# Half_Slave.net
KiCad netlist of a schematic drawn in Altium Designer
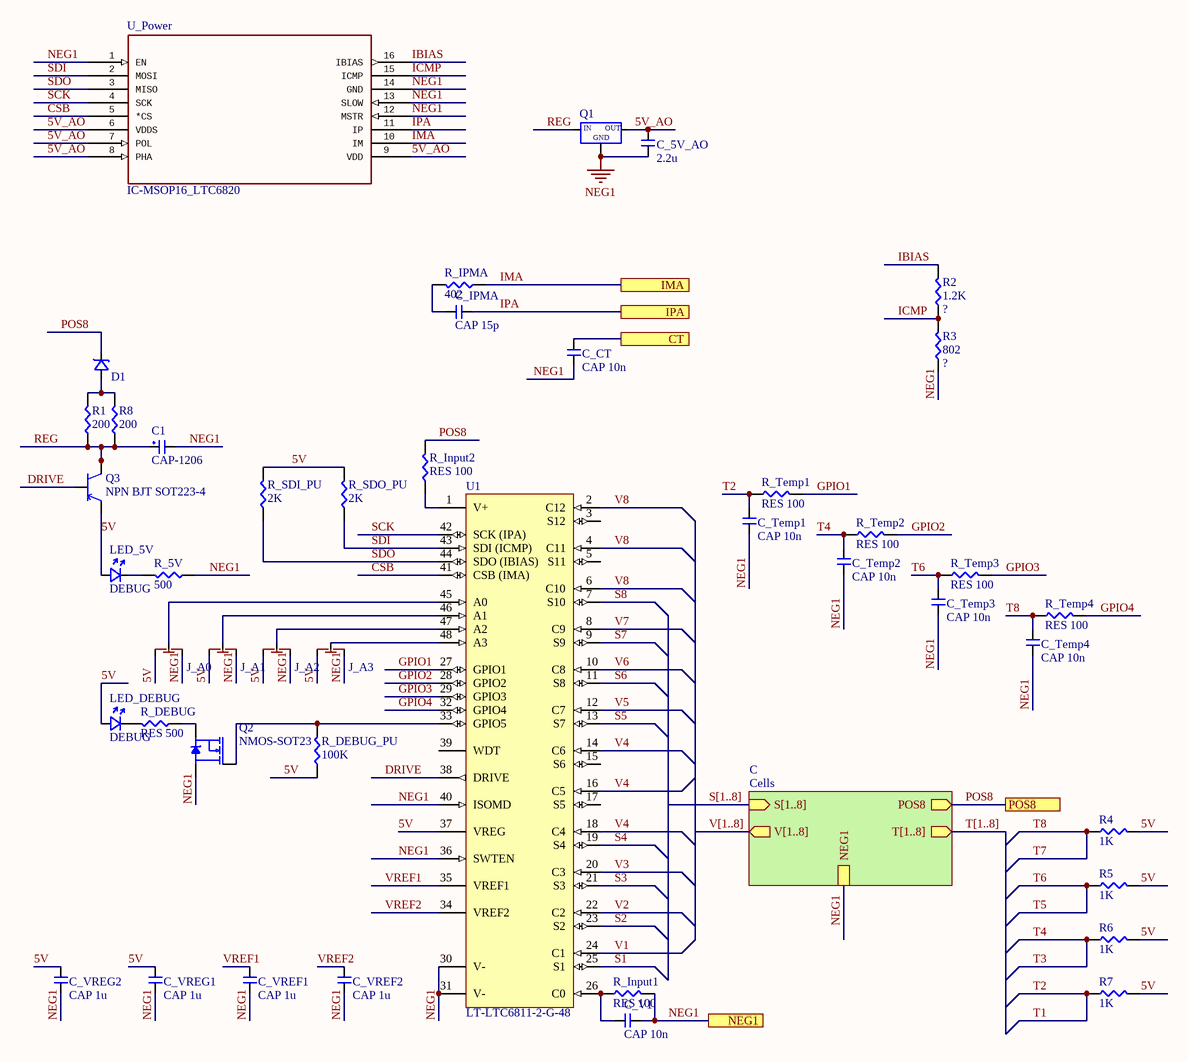
[diagram p0: Half_Slave.SchDoc]

(export (version "E")
  (design (tool "Eeschema 10.0.6"))
  (components
    (comp (ref "C1")
      (value "CAP-1206")
      (footprint "CAPCP3216X16N")
      (libsource (lib "LTC6811") (part "CAP-1206"))
    )
    (comp (ref "C_5V_AO")
      (value "2.2u")
      (footprint "CAP-0603")
      (description "CAP-0603")
      (libsource (lib "ife19_Elec_Library") (part "CAP-0603"))
    )
    (comp (ref "C_CT")
      (value "CAP 10n")
      (footprint "CAP-0603")
      (description "CAP-0603")
      (libsource (lib "ife18_TS_BMS_LTC6813_v2_Library") (part "CAP-0603"))
    )
    (comp (ref "C_IPMA")
      (value "CAP 15p")
      (footprint "CAP-0603")
      (description "CAP-0603")
      (libsource (lib "ife19_Elec_Library") (part "CAP-0603"))
    )
    (comp (ref "C_Temp1")
      (value "CAP 10n")
      (footprint "CAP-0603")
      (description "CAP-0603")
      (libsource (lib "altium-import") (part "root_1_CAP-0603_"))
    )
    (comp (ref "C_Temp2")
      (value "CAP 10n")
      (footprint "CAP-0603")
      (description "CAP-0603")
      (libsource (lib "altium-import") (part "root_1_CAP-0603_"))
    )
    (comp (ref "C_Temp3")
      (value "CAP 10n")
      (footprint "CAP-0603")
      (description "CAP-0603")
      (libsource (lib "altium-import") (part "root_1_CAP-0603_"))
    )
    (comp (ref "C_Temp4")
      (value "CAP 10n")
      (footprint "CAP-0603")
      (description "CAP-0603")
      (libsource (lib "altium-import") (part "root_1_CAP-0603_"))
    )
    (comp (ref "C_V1")
      (value "CAP 10n")
      (footprint "CAP-0603")
      (description "CAP-0603")
      (libsource (lib "altium-import") (part "root_2_CAP-0603_"))
    )
    (comp (ref "C_VREF1")
      (value "CAP 1u")
      (footprint "CAP-0603")
      (description "CAP-0603")
      (libsource (lib "altium-import") (part "root_1_CAP-0603_"))
    )
    (comp (ref "C_VREF2")
      (value "CAP 1u")
      (footprint "CAP-0603")
      (description "CAP-0603")
      (libsource (lib "altium-import") (part "root_1_CAP-0603_"))
    )
    (comp (ref "C_VREG1")
      (value "CAP 1u")
      (footprint "CAP-0603")
      (description "CAP-0603")
      (libsource (lib "altium-import") (part "root_1_CAP-0603_"))
    )
    (comp (ref "C_VREG2")
      (value "CAP 1u")
      (footprint "CAP-0603")
      (description "CAP-0603")
      (libsource (lib "altium-import") (part "root_1_CAP-0603_"))
    )
    (comp (ref "D1") (value "?") (footprint "SMB") (libsource (lib "ife19_Elec_Library") (part "DIODE-SMB")))
    (comp (ref "J_A0")
      (value "DPDT Solder Jumper")
      (footprint "DPDT Solder")
      (libsource (lib "LTC6811") (part "DPDT Solder"))
    )
    (comp (ref "J_A1")
      (value "DPDT Solder Jumper")
      (footprint "DPDT Solder")
      (libsource (lib "LTC6811") (part "DPDT Solder"))
    )
    (comp (ref "J_A2")
      (value "DPDT Solder Jumper")
      (footprint "DPDT Solder")
      (libsource (lib "LTC6811") (part "DPDT Solder"))
    )
    (comp (ref "J_A3")
      (value "DPDT Solder Jumper")
      (footprint "DPDT Solder")
      (libsource (lib "LTC6811") (part "DPDT Solder"))
    )
    (comp (ref "LED_5V")
      (value "DEBUG")
      (footprint "LED-0603")
      (description "LED-0603")
      (libsource (lib "altium-import") (part "root_0_LED-0603_"))
    )
    (comp (ref "LED_DEBUG")
      (value "DEBUG")
      (footprint "LED-0603")
      (description "LED-0603")
      (libsource (lib "altium-import") (part "root_0_LED-0603_"))
    )
    (comp (ref "Q1")
      (value "5V LDO")
      (footprint "SOT23-5")
      (libsource (lib "ife19_Elec_Library") (part "LDO-SOT23-TPS7B69"))
    )
    (comp (ref "Q2")
      (value "NMOS-SOT23")
      (footprint "SOT23")
      (libsource (lib "ife19_Elec_Library") (part "NMOS-SOT23"))
    )
    (comp (ref "Q3")
      (value "NPN BJT SOT223-4")
      (footprint "SOT223")
      (description "BCP54,115")
      (libsource (lib "ife19_Elec_Library") (part "NPN_SOT223-4"))
    )
    (comp (ref "R1")
      (value "200")
      (footprint "RES-0603")
      (libsource (lib "ife18_TS_BMS_LTC6813_v2_Library") (part "RES-0603"))
    )
    (comp (ref "R2")
      (value "1.2K")
      (footprint "RES-0603")
      (description "RES SMD 0603")
      (fields (field (name "PART") "RES_0603") (field (name "ALTIUM_VALUE") "?"))
      (libsource (lib "IFE") (part "RES"))
    )
    (comp (ref "R3")
      (value "802")
      (footprint "RES-0603")
      (description "RES SMD 0603")
      (fields (field (name "PART") "RES_0603") (field (name "ALTIUM_VALUE") "?"))
      (libsource (lib "IFE") (part "RES"))
    )
    (comp (ref "R4")
      (value "1K")
      (footprint "RES-0603")
      (libsource (lib "ife19_Elec_Library") (part "RES-0603"))
    )
    (comp (ref "R5")
      (value "1K")
      (footprint "RES-0603")
      (libsource (lib "ife19_Elec_Library") (part "RES-0603"))
    )
    (comp (ref "R6")
      (value "1K")
      (footprint "RES-0603")
      (libsource (lib "ife19_Elec_Library") (part "RES-0603"))
    )
    (comp (ref "R7")
      (value "1K")
      (footprint "RES-0603")
      (libsource (lib "ife19_Elec_Library") (part "RES-0603"))
    )
    (comp (ref "R8")
      (value "200")
      (footprint "RES-0603")
      (libsource (lib "ife18_TS_BMS_LTC6813_v2_Library") (part "RES-0603"))
    )
    (comp (ref "R_5V")
      (value "500")
      (footprint "RES-0603")
      (libsource (lib "altium-import") (part "root_2_RES-0603_"))
    )
    (comp (ref "R_DEBUG")
      (value "RES 500")
      (footprint "RES-0603")
      (libsource (lib "altium-import") (part "root_2_RES-0603_"))
    )
    (comp (ref "R_DEBUG_PU")
      (value "100K")
      (footprint "RES-0603")
      (libsource (lib "ife18_TS_BMS_LTC6813_v2_Library") (part "RES-0603"))
    )
    (comp (ref "R_Input1")
      (value "RES 100")
      (footprint "RES-0603")
      (libsource (lib "altium-import") (part "root_0_RES-0603_"))
    )
    (comp (ref "R_Input2")
      (value "RES 100")
      (footprint "RES-0603")
      (libsource (lib "altium-import") (part "root_1_RES-0603_"))
    )
    (comp (ref "R_IPMA")
      (value "402")
      (footprint "RES-0603")
      (libsource (lib "ife19_Elec_Library") (part "RES-0603"))
    )
    (comp (ref "R_SDI_PU")
      (value "2K")
      (footprint "RES-0603")
      (libsource (lib "ife18_TS_BMS_LTC6813_v2_Library") (part "RES-0603"))
    )
    (comp (ref "R_SDO_PU")
      (value "2K")
      (footprint "RES-0603")
      (libsource (lib "ife18_TS_BMS_LTC6813_v2_Library") (part "RES-0603"))
    )
    (comp (ref "R_Temp1")
      (value "RES 100")
      (footprint "RES-0603")
      (libsource (lib "altium-import") (part "root_0_RES-0603_"))
    )
    (comp (ref "R_Temp2")
      (value "RES 100")
      (footprint "RES-0603")
      (libsource (lib "altium-import") (part "root_0_RES-0603_"))
    )
    (comp (ref "R_Temp3")
      (value "RES 100")
      (footprint "RES-0603")
      (libsource (lib "altium-import") (part "root_0_RES-0603_"))
    )
    (comp (ref "R_Temp4")
      (value "RES 100")
      (footprint "RES-0603")
      (libsource (lib "altium-import") (part "root_0_RES-0603_"))
    )
    (comp (ref "U1")
      (value "LT-LTC6811-2-G-48")
      (footprint "SSOP-48N")
      (libsource (lib "LTC6811") (part "LT-LTC6811-2-G-48"))
    )
    (comp (ref "U_Power")
      (value "IC-MSOP16_LTC6820")
      (footprint "MSOP16")
      (libsource (lib "ife19_Elec_Library") (part "IC-MSOP16_LTC6820"))
    )
  )
  (nets
    (net (code "1") (name "/5V") (class "Default")
      (node (ref "C_VREG1") (pin "2") (pinfunction "2_2") (pintype "passive"))
      (node (ref "C_VREG2") (pin "2") (pinfunction "2_2") (pintype "passive"))
      (node (ref "J_A0") (pin "2") (pintype "passive"))
      (node (ref "J_A1") (pin "2") (pintype "passive"))
      (node (ref "J_A2") (pin "2") (pintype "passive"))
      (node (ref "J_A3") (pin "2") (pintype "passive"))
      (node (ref "LED_5V") (pin "A") (pinfunction "A_A") (pintype "passive"))
      (node (ref "LED_DEBUG") (pin "A") (pinfunction "A_A") (pintype "passive"))
      (node (ref "Q3") (pin "3") (pinfunction "E_3") (pintype "passive"))
      (node (ref "R4") (pin "2") (pinfunction "2_2") (pintype "passive"))
      (node (ref "R5") (pin "2") (pinfunction "2_2") (pintype "passive"))
      (node (ref "R6") (pin "2") (pinfunction "2_2") (pintype "passive"))
      (node (ref "R7") (pin "2") (pinfunction "2_2") (pintype "passive"))
      (node (ref "R_DEBUG_PU") (pin "1") (pinfunction "1_1") (pintype "passive"))
      (node (ref "R_SDI_PU") (pin "2") (pinfunction "2_2") (pintype "passive"))
      (node (ref "R_SDO_PU") (pin "2") (pinfunction "2_2") (pintype "passive"))
      (node (ref "U1") (pin "37") (pinfunction "VREG_37") (pintype "power_in"))
    )
    (net (code "2") (name "/5V_AO") (class "Default")
      (node (ref "C_5V_AO") (pin "1") (pinfunction "1_1") (pintype "passive"))
      (node (ref "Q1") (pin "5") (pinfunction "OUT_5") (pintype "passive"))
      (node (ref "U_Power") (pin "6") (pinfunction "VDDS_6") (pintype "power_in"))
      (node (ref "U_Power") (pin "7") (pinfunction "POL_7") (pintype "input"))
      (node (ref "U_Power") (pin "8") (pinfunction "PHA_8") (pintype "input"))
      (node (ref "U_Power") (pin "9") (pinfunction "VDD_9") (pintype "power_in"))
    )
    (net (code "3") (name "/CSB") (class "Default")
      (node (ref "U1") (pin "41") (pinfunction "CSB_(IMA)_41") (pintype "bidirectional"))
      (node (ref "U_Power") (pin "5") (pinfunction "*CS_5") (pintype "passive"))
    )
    (net (code "4") (name "/CT") (class "Default")
      (node (ref "C_CT") (pin "1") (pinfunction "1_1") (pintype "passive"))
    )
    (net (code "5") (name "/DRIVE") (class "Default")
      (node (ref "Q3") (pin "1") (pinfunction "B_1") (pintype "passive"))
      (node (ref "U1") (pin "38") (pinfunction "DRIVE_38") (pintype "output"))
    )
    (net (code "6") (name "/GPIO1") (class "Default")
      (node (ref "R_Temp1") (pin "2") (pinfunction "2_2") (pintype "passive"))
      (node (ref "U1") (pin "27") (pinfunction "GPIO1_27") (pintype "bidirectional"))
    )
    (net (code "7") (name "/GPIO2") (class "Default")
      (node (ref "R_Temp2") (pin "2") (pinfunction "2_2") (pintype "passive"))
      (node (ref "U1") (pin "28") (pinfunction "GPIO2_28") (pintype "bidirectional"))
    )
    (net (code "8") (name "/GPIO3") (class "Default")
      (node (ref "R_Temp3") (pin "2") (pinfunction "2_2") (pintype "passive"))
      (node (ref "U1") (pin "29") (pinfunction "GPIO3_29") (pintype "bidirectional"))
    )
    (net (code "9") (name "/GPIO4") (class "Default")
      (node (ref "R_Temp4") (pin "2") (pinfunction "2_2") (pintype "passive"))
      (node (ref "U1") (pin "32") (pinfunction "GPIO4_32") (pintype "bidirectional"))
    )
    (net (code "10") (name "/IBIAS") (class "Default")
      (node (ref "R2") (pin "2") (pinfunction "2_2") (pintype "passive"))
      (node (ref "U_Power") (pin "16") (pinfunction "IBIAS_16") (pintype "output"))
    )
    (net (code "11") (name "/ICMP") (class "Default")
      (node (ref "R2") (pin "1") (pinfunction "1_1") (pintype "passive"))
      (node (ref "R3") (pin "2") (pinfunction "2_2") (pintype "passive"))
      (node (ref "U_Power") (pin "15") (pinfunction "ICMP_15") (pintype "passive"))
    )
    (net (code "12") (name "/IMA") (class "Default")
      (node (ref "R_IPMA") (pin "1") (pinfunction "1_1") (pintype "passive"))
      (node (ref "U_Power") (pin "10") (pinfunction "IM_10") (pintype "passive"))
    )
    (net (code "13") (name "/IPA") (class "Default")
      (node (ref "C_IPMA") (pin "1") (pinfunction "1_1") (pintype "passive"))
      (node (ref "U_Power") (pin "11") (pinfunction "IP_11") (pintype "passive"))
    )
    (net (code "14") (name "/POS8") (class "Default")
      (node (ref "D1") (pin "K") (pinfunction "K_K") (pintype "passive"))
      (node (ref "R_Input2") (pin "2") (pinfunction "2_2") (pintype "passive"))
    )
    (net (code "15") (name "/REG") (class "Default")
      (node (ref "C1") (pin "1") (pinfunction "1_1") (pintype "passive"))
      (node (ref "Q1") (pin "1") (pinfunction "IN_1") (pintype "passive"))
      (node (ref "Q3") (pin "2") (pinfunction "C_2") (pintype "passive"))
      (node (ref "Q3") (pin "4") (pinfunction "C_4") (pintype "passive"))
      (node (ref "R1") (pin "1") (pinfunction "1_1") (pintype "passive"))
      (node (ref "R8") (pin "1") (pinfunction "1_1") (pintype "passive"))
    )
    (net (code "16") (name "/S1") (class "Default")
      (node (ref "U1") (pin "25") (pinfunction "S1_25") (pintype "bidirectional"))
    )
    (net (code "17") (name "/S2") (class "Default")
      (node (ref "U1") (pin "23") (pinfunction "S2_23") (pintype "bidirectional"))
    )
    (net (code "18") (name "/S3") (class "Default")
      (node (ref "U1") (pin "21") (pinfunction "S3_21") (pintype "bidirectional"))
    )
    (net (code "19") (name "/S4") (class "Default")
      (node (ref "U1") (pin "19") (pinfunction "S4_19") (pintype "bidirectional"))
    )
    (net (code "20") (name "/S5") (class "Default")
      (node (ref "U1") (pin "13") (pinfunction "S7_13") (pintype "bidirectional"))
    )
    (net (code "21") (name "/S6") (class "Default")
      (node (ref "U1") (pin "11") (pinfunction "S8_11") (pintype "bidirectional"))
    )
    (net (code "22") (name "/S7") (class "Default")
      (node (ref "U1") (pin "9") (pinfunction "S9_9") (pintype "bidirectional"))
    )
    (net (code "23") (name "/S8") (class "Default")
      (node (ref "U1") (pin "7") (pinfunction "S10_7") (pintype "bidirectional"))
    )
    (net (code "24") (name "/SCK") (class "Default")
      (node (ref "U1") (pin "42") (pinfunction "SCK_(IPA)_42") (pintype "bidirectional"))
      (node (ref "U_Power") (pin "4") (pinfunction "SCK_4") (pintype "passive"))
    )
    (net (code "25") (name "/SDI") (class "Default")
      (node (ref "R_SDO_PU") (pin "1") (pinfunction "1_1") (pintype "passive"))
      (node (ref "U1") (pin "43") (pinfunction "SDI_(ICMP)_43") (pintype "input"))
      (node (ref "U_Power") (pin "2") (pinfunction "MOSI_2") (pintype "passive"))
    )
    (net (code "26") (name "/SDO") (class "Default")
      (node (ref "R_SDI_PU") (pin "1") (pinfunction "1_1") (pintype "passive"))
      (node (ref "U1") (pin "44") (pinfunction "SDO_(IBIAS)_44") (pintype "bidirectional"))
      (node (ref "U_Power") (pin "3") (pinfunction "MISO_3") (pintype "passive"))
    )
    (net (code "28") (name "/T2") (class "Default")
      (node (ref "C_Temp1") (pin "2") (pinfunction "2_2") (pintype "passive"))
      (node (ref "R7") (pin "1") (pinfunction "1_1") (pintype "passive"))
      (node (ref "R_Temp1") (pin "1") (pinfunction "1_1") (pintype "passive"))
    )
    (net (code "29") (name "/T4") (class "Default")
      (node (ref "C_Temp2") (pin "2") (pinfunction "2_2") (pintype "passive"))
      (node (ref "R6") (pin "1") (pinfunction "1_1") (pintype "passive"))
      (node (ref "R_Temp2") (pin "1") (pinfunction "1_1") (pintype "passive"))
    )
    (net (code "30") (name "/T6") (class "Default")
      (node (ref "C_Temp3") (pin "2") (pinfunction "2_2") (pintype "passive"))
      (node (ref "R5") (pin "1") (pinfunction "1_1") (pintype "passive"))
      (node (ref "R_Temp3") (pin "1") (pinfunction "1_1") (pintype "passive"))
    )
    (net (code "31") (name "/T8") (class "Default")
      (node (ref "C_Temp4") (pin "2") (pinfunction "2_2") (pintype "passive"))
      (node (ref "R4") (pin "1") (pinfunction "1_1") (pintype "passive"))
      (node (ref "R_Temp4") (pin "1") (pinfunction "1_1") (pintype "passive"))
    )
    (net (code "33") (name "/V1") (class "Default")
      (node (ref "U1") (pin "24") (pinfunction "C1_24") (pintype "input"))
    )
    (net (code "34") (name "/V2") (class "Default")
      (node (ref "U1") (pin "22") (pinfunction "C2_22") (pintype "input"))
    )
    (net (code "35") (name "/V3") (class "Default")
      (node (ref "U1") (pin "20") (pinfunction "C3_20") (pintype "input"))
    )
    (net (code "36") (name "/V4") (class "Default")
      (node (ref "U1") (pin "14") (pinfunction "C6_14") (pintype "input"))
      (node (ref "U1") (pin "16") (pinfunction "C5_16") (pintype "input"))
      (node (ref "U1") (pin "18") (pinfunction "C4_18") (pintype "input"))
    )
    (net (code "37") (name "/V5") (class "Default")
      (node (ref "U1") (pin "12") (pinfunction "C7_12") (pintype "input"))
    )
    (net (code "38") (name "/V6") (class "Default")
      (node (ref "U1") (pin "10") (pinfunction "C8_10") (pintype "input"))
    )
    (net (code "39") (name "/V7") (class "Default")
      (node (ref "U1") (pin "8") (pinfunction "C9_8") (pintype "input"))
    )
    (net (code "40") (name "/V8") (class "Default")
      (node (ref "U1") (pin "2") (pinfunction "C12_2") (pintype "input"))
      (node (ref "U1") (pin "4") (pinfunction "C11_4") (pintype "input"))
      (node (ref "U1") (pin "6") (pinfunction "C10_6") (pintype "input"))
    )
    (net (code "41") (name "/VREF1") (class "Default")
      (node (ref "C_VREF1") (pin "2") (pinfunction "2_2") (pintype "passive"))
      (node (ref "U1") (pin "35") (pinfunction "VREF1_35") (pintype "passive"))
    )
    (net (code "42") (name "/VREF2") (class "Default")
      (node (ref "C_VREF2") (pin "2") (pinfunction "2_2") (pintype "passive"))
      (node (ref "U1") (pin "34") (pinfunction "VREF2_34") (pintype "passive"))
    )
    (net (code "44") (name "NEG1") (class "Default")
      (node (ref "C1") (pin "2") (pinfunction "2_2") (pintype "passive"))
      (node (ref "C_5V_AO") (pin "2") (pinfunction "2_2") (pintype "passive"))
      (node (ref "C_CT") (pin "2") (pinfunction "2_2") (pintype "passive"))
      (node (ref "C_Temp1") (pin "1") (pinfunction "1_1") (pintype "passive"))
      (node (ref "C_Temp2") (pin "1") (pinfunction "1_1") (pintype "passive"))
      (node (ref "C_Temp3") (pin "1") (pinfunction "1_1") (pintype "passive"))
      (node (ref "C_Temp4") (pin "1") (pinfunction "1_1") (pintype "passive"))
      (node (ref "C_V1") (pin "1") (pinfunction "1_1") (pintype "passive"))
      (node (ref "C_VREF1") (pin "1") (pinfunction "1_1") (pintype "passive"))
      (node (ref "C_VREF2") (pin "1") (pinfunction "1_1") (pintype "passive"))
      (node (ref "C_VREG1") (pin "1") (pinfunction "1_1") (pintype "passive"))
      (node (ref "C_VREG2") (pin "1") (pinfunction "1_1") (pintype "passive"))
      (node (ref "J_A0") (pin "1") (pintype "passive"))
      (node (ref "J_A1") (pin "1") (pintype "passive"))
      (node (ref "J_A2") (pin "1") (pintype "passive"))
      (node (ref "J_A3") (pin "1") (pintype "passive"))
      (node (ref "Q1") (pin "2") (pinfunction "GND_2") (pintype "passive"))
      (node (ref "Q1") (pin "3") (pinfunction "GND_3") (pintype "passive"))
      (node (ref "Q1") (pin "4") (pinfunction "GND_4") (pintype "passive"))
      (node (ref "Q2") (pin "2") (pinfunction "S_2") (pintype "passive"))
      (node (ref "R3") (pin "1") (pinfunction "1_1") (pintype "passive"))
      (node (ref "R_5V") (pin "1") (pinfunction "1_1") (pintype "passive"))
      (node (ref "R_Input1") (pin "2") (pinfunction "2_2") (pintype "passive"))
      (node (ref "U1") (pin "30") (pinfunction "V-_30") (pintype "power_in"))
      (node (ref "U1") (pin "31") (pinfunction "V-_31") (pintype "power_in"))
      (node (ref "U1") (pin "36") (pinfunction "SWTEN_36") (pintype "input"))
      (node (ref "U1") (pin "40") (pinfunction "ISOMD_40") (pintype "input"))
      (node (ref "U_Power") (pin "1") (pinfunction "EN_1") (pintype "input"))
      (node (ref "U_Power") (pin "12") (pinfunction "MSTR_12") (pintype "input"))
      (node (ref "U_Power") (pin "13") (pinfunction "SLOW_13") (pintype "input"))
      (node (ref "U_Power") (pin "14") (pinfunction "GND_14") (pintype "power_in"))
    )
    (net (code "45") (name "Net-(C_IPMA-Pad2)") (class "Default")
      (node (ref "C_IPMA") (pin "2") (pinfunction "2_2") (pintype "passive"))
      (node (ref "R_IPMA") (pin "2") (pinfunction "2_2") (pintype "passive"))
    )
    (net (code "46") (name "Net-(D1-PadA)") (class "Default")
      (node (ref "D1") (pin "A") (pinfunction "A_A") (pintype "passive"))
      (node (ref "R1") (pin "2") (pinfunction "2_2") (pintype "passive"))
      (node (ref "R8") (pin "2") (pinfunction "2_2") (pintype "passive"))
    )
    (net (code "47") (name "Net-(LED_5V-PadK)") (class "Default")
      (node (ref "LED_5V") (pin "K") (pinfunction "K_K") (pintype "passive"))
      (node (ref "R_5V") (pin "2") (pinfunction "2_2") (pintype "passive"))
    )
    (net (code "48") (name "Net-(LED_DEBUG-PadK)") (class "Default")
      (node (ref "LED_DEBUG") (pin "K") (pinfunction "K_K") (pintype "passive"))
      (node (ref "R_DEBUG") (pin "2") (pinfunction "2_2") (pintype "passive"))
    )
    (net (code "49") (name "Net-(Q2-D)") (class "Default")
      (node (ref "Q2") (pin "3") (pinfunction "D_3") (pintype "passive"))
      (node (ref "R_DEBUG") (pin "1") (pinfunction "1_1") (pintype "passive"))
    )
    (net (code "50") (name "Net-(Q2-G)") (class "Default")
      (node (ref "Q2") (pin "1") (pinfunction "G_1") (pintype "passive"))
      (node (ref "R_DEBUG_PU") (pin "2") (pinfunction "2_2") (pintype "passive"))
      (node (ref "U1") (pin "33") (pinfunction "GPIO5_33") (pintype "bidirectional"))
    )
    (net (code "51") (name "Net-(U1-A0)") (class "Default")
      (node (ref "J_A0") (pin "3") (pintype "passive"))
      (node (ref "U1") (pin "45") (pinfunction "A0_45") (pintype "input"))
    )
    (net (code "52") (name "Net-(U1-A1)") (class "Default")
      (node (ref "J_A1") (pin "3") (pintype "passive"))
      (node (ref "U1") (pin "46") (pinfunction "A1_46") (pintype "input"))
    )
    (net (code "53") (name "Net-(U1-A2)") (class "Default")
      (node (ref "J_A2") (pin "3") (pintype "passive"))
      (node (ref "U1") (pin "47") (pinfunction "A2_47") (pintype "input"))
    )
    (net (code "54") (name "Net-(U1-A3)") (class "Default")
      (node (ref "J_A3") (pin "3") (pintype "passive"))
      (node (ref "U1") (pin "48") (pinfunction "A3_48") (pintype "input"))
    )
    (net (code "55") (name "Net-(U1-C0)") (class "Default")
      (node (ref "C_V1") (pin "2") (pinfunction "2_2") (pintype "passive"))
      (node (ref "R_Input1") (pin "1") (pinfunction "1_1") (pintype "passive"))
      (node (ref "U1") (pin "26") (pinfunction "C0_26") (pintype "input"))
    )
    (net (code "56") (name "Net-(U1-V+)") (class "Default")
      (node (ref "R_Input2") (pin "1") (pinfunction "1_1") (pintype "passive"))
      (node (ref "U1") (pin "1") (pinfunction "V+_1") (pintype "power_in"))
    )
    (net (code "57") (name "unconnected-(U1-S5-Pad17)") (class "Default")
      (node (ref "U1") (pin "17") (pinfunction "S5_17") (pintype "bidirectional"))
    )
    (net (code "58") (name "unconnected-(U1-S6-Pad15)") (class "Default")
      (node (ref "U1") (pin "15") (pinfunction "S6_15") (pintype "bidirectional"))
    )
    (net (code "59") (name "unconnected-(U1-S11-Pad5)") (class "Default")
      (node (ref "U1") (pin "5") (pinfunction "S11_5") (pintype "bidirectional"))
    )
    (net (code "60") (name "unconnected-(U1-S12-Pad3)") (class "Default")
      (node (ref "U1") (pin "3") (pinfunction "S12_3") (pintype "bidirectional"))
    )
    (net (code "61") (name "unconnected-(U1-WDT-Pad39)") (class "Default")
      (node (ref "U1") (pin "39") (pinfunction "WDT_39") (pintype "tri_state"))
    )
  )
)
